# contra4688.net
KiCad netlist of a schematic drawn in EAGLE
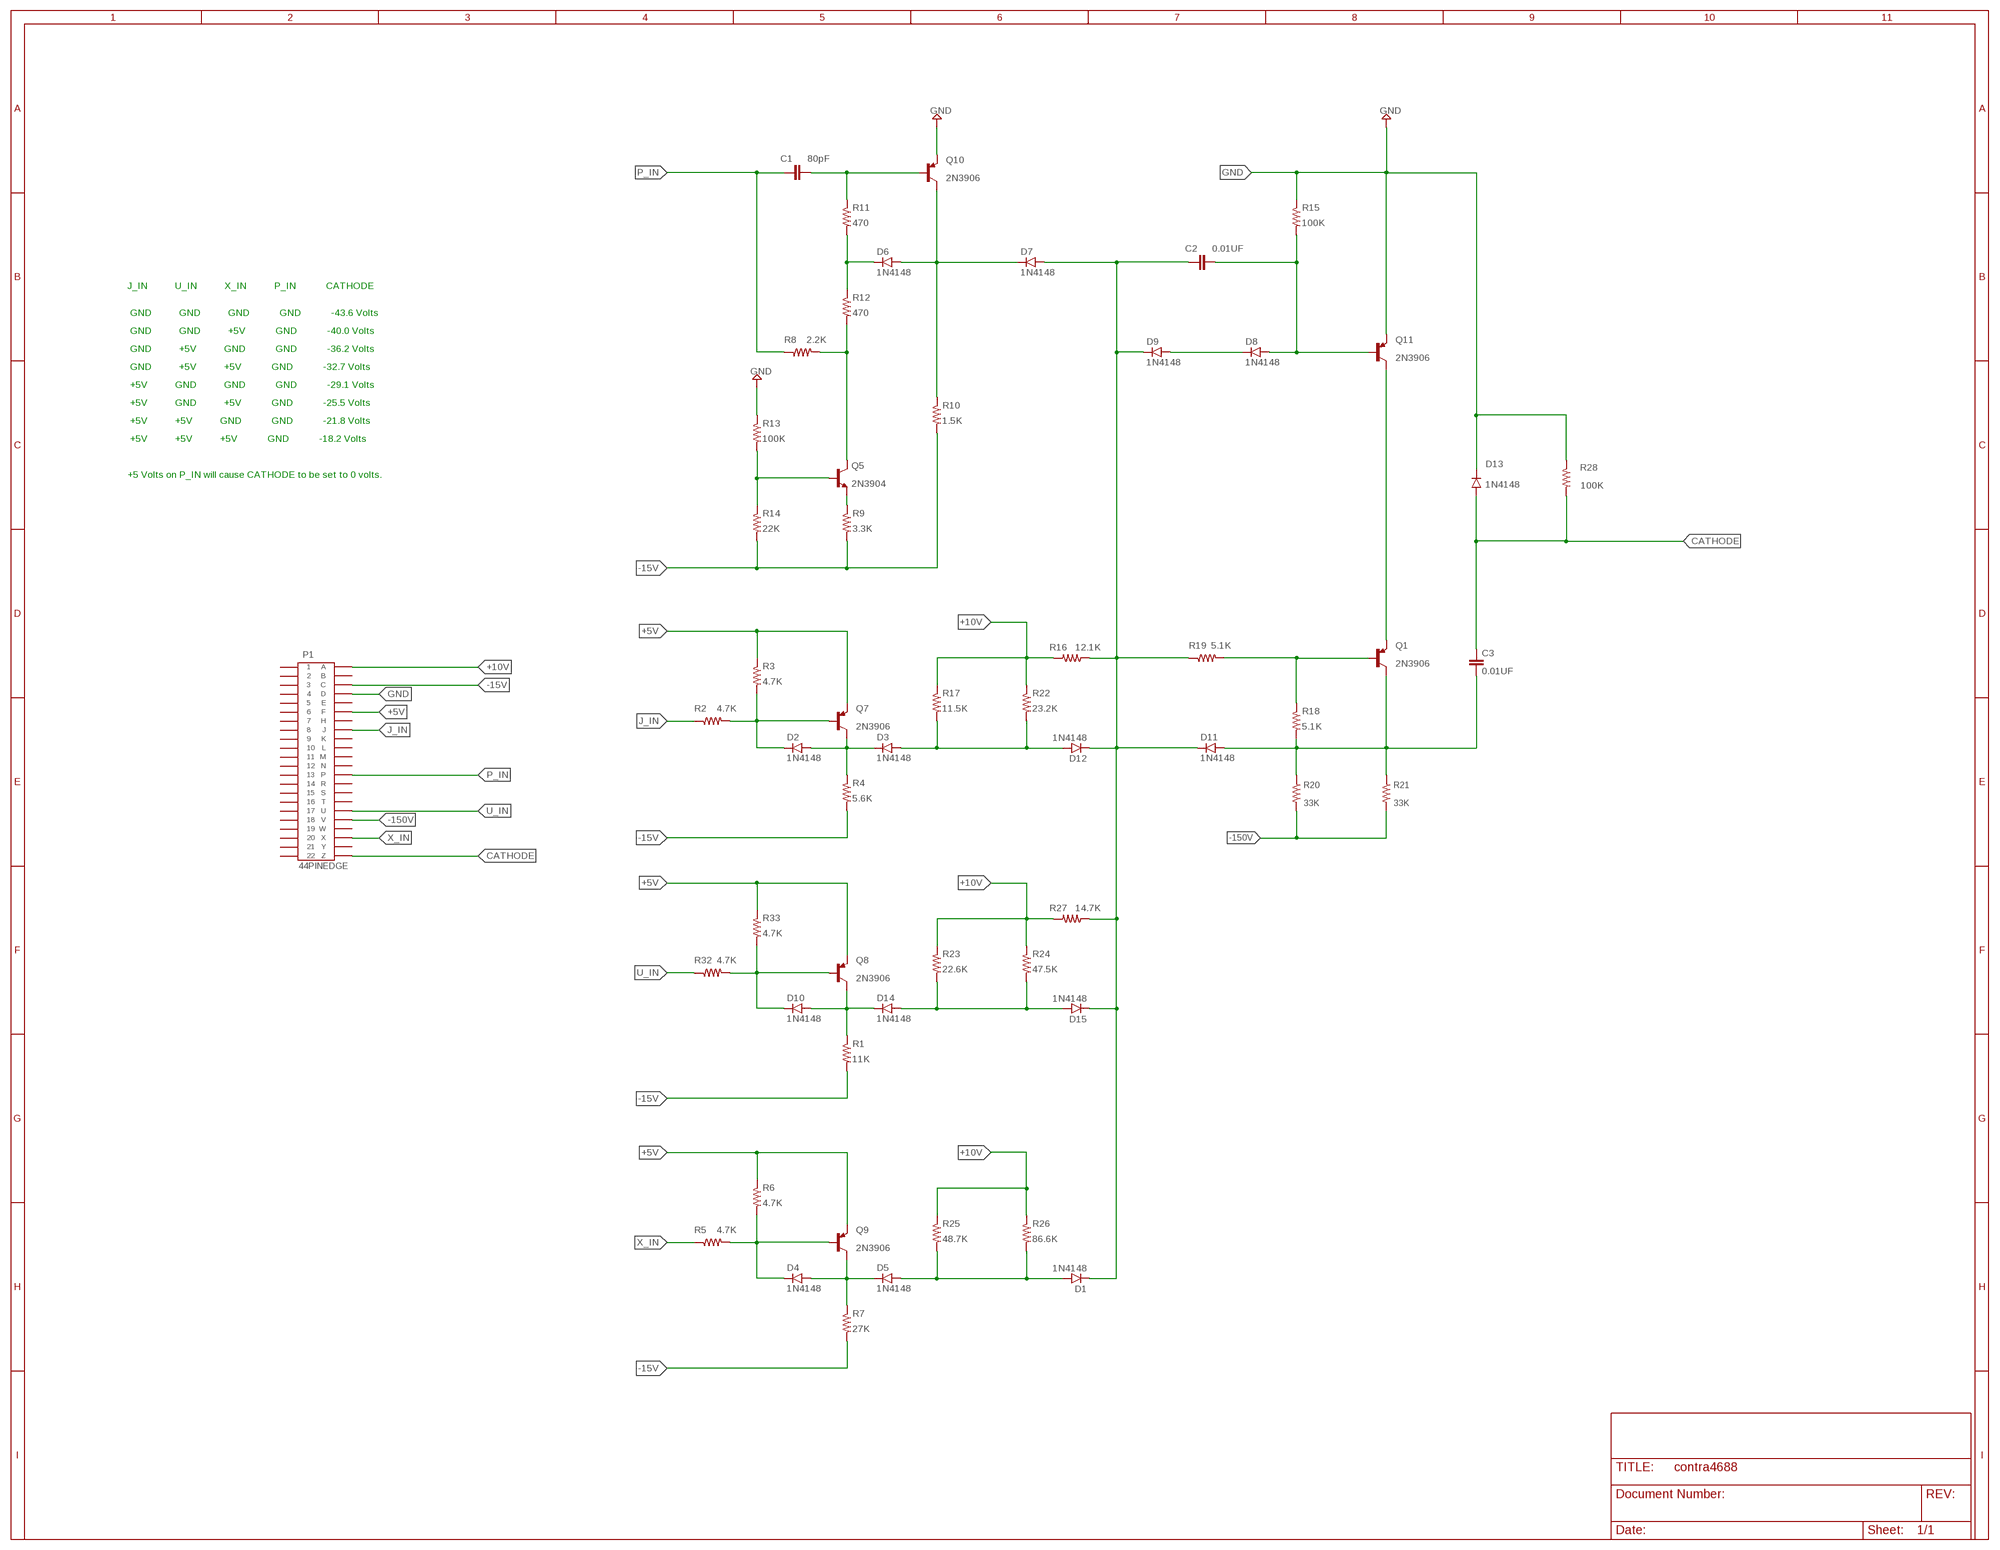
[diagram p0: schematic, sheet 1]

(export (version "E")
  (design (tool "Eeschema 10.0.6"))
  (components
    (comp (ref "C1")
      (value "80pF")
      (footprint "eagle-import:5MM_TH")
      (libsource (lib "eagle-import") (part "CAP_5MM"))
    )
    (comp (ref "C2")
      (value "0.01UF")
      (footprint "eagle-import:5MM_TH")
      (libsource (lib "eagle-import") (part "CAP_5MM"))
    )
    (comp (ref "C3")
      (value "0.01UF")
      (footprint "eagle-import:5MM_TH")
      (libsource (lib "eagle-import") (part "CAP_5MM"))
    )
    (comp (ref "D1")
      (value "1N4148")
      (footprint "eagle-import:DO35-7")
      (libsource (lib "eagle-import") (part "1N4148"))
    )
    (comp (ref "D2")
      (value "1N4148")
      (footprint "eagle-import:DO35-7")
      (libsource (lib "eagle-import") (part "1N4148"))
    )
    (comp (ref "D3")
      (value "1N4148")
      (footprint "eagle-import:DO35-7")
      (libsource (lib "eagle-import") (part "1N4148"))
    )
    (comp (ref "D4")
      (value "1N4148")
      (footprint "eagle-import:DO35-7")
      (libsource (lib "eagle-import") (part "1N4148"))
    )
    (comp (ref "D5")
      (value "1N4148")
      (footprint "eagle-import:DO35-7")
      (libsource (lib "eagle-import") (part "1N4148"))
    )
    (comp (ref "D6")
      (value "1N4148")
      (footprint "eagle-import:DO35-7")
      (libsource (lib "eagle-import") (part "1N4148"))
    )
    (comp (ref "D7")
      (value "1N4148")
      (footprint "eagle-import:DO35-7")
      (libsource (lib "eagle-import") (part "1N4148"))
    )
    (comp (ref "D8")
      (value "1N4148")
      (footprint "eagle-import:DO35-7")
      (libsource (lib "eagle-import") (part "1N4148"))
    )
    (comp (ref "D9")
      (value "1N4148")
      (footprint "eagle-import:DO35-7")
      (libsource (lib "eagle-import") (part "1N4148"))
    )
    (comp (ref "D10")
      (value "1N4148")
      (footprint "eagle-import:DO35-7")
      (libsource (lib "eagle-import") (part "1N4148"))
    )
    (comp (ref "D11")
      (value "1N4148")
      (footprint "eagle-import:DO35-7")
      (libsource (lib "eagle-import") (part "1N4148"))
    )
    (comp (ref "D12")
      (value "1N4148")
      (footprint "eagle-import:DO35-7")
      (libsource (lib "eagle-import") (part "1N4148"))
    )
    (comp (ref "D13")
      (value "1N4148")
      (footprint "eagle-import:DO35-7")
      (libsource (lib "eagle-import") (part "1N4148"))
    )
    (comp (ref "D14")
      (value "1N4148")
      (footprint "eagle-import:DO35-7")
      (libsource (lib "eagle-import") (part "1N4148"))
    )
    (comp (ref "D15")
      (value "1N4148")
      (footprint "eagle-import:DO35-7")
      (libsource (lib "eagle-import") (part "1N4148"))
    )
    (comp (ref "P1")
      (value "44PINEDGE")
      (footprint "eagle-import:44PINEDGE")
      (libsource (lib "eagle-import") (part "44PINEDGE"))
    )
    (comp (ref "Q1")
      (value "2N3906")
      (footprint "eagle-import:TO92")
      (libsource (lib "eagle-import") (part "2N3906"))
    )
    (comp (ref "Q5")
      (value "2N3904")
      (footprint "eagle-import:TO92")
      (libsource (lib "eagle-import") (part "2N3904"))
    )
    (comp (ref "Q7")
      (value "2N3906")
      (footprint "eagle-import:TO92")
      (libsource (lib "eagle-import") (part "2N3906"))
    )
    (comp (ref "Q8")
      (value "2N3906")
      (footprint "eagle-import:TO92")
      (libsource (lib "eagle-import") (part "2N3906"))
    )
    (comp (ref "Q9")
      (value "2N3906")
      (footprint "eagle-import:TO92")
      (libsource (lib "eagle-import") (part "2N3906"))
    )
    (comp (ref "Q10")
      (value "2N3906")
      (footprint "eagle-import:TO92")
      (libsource (lib "eagle-import") (part "2N3906"))
    )
    (comp (ref "Q11")
      (value "2N3906")
      (footprint "eagle-import:TO92")
      (libsource (lib "eagle-import") (part "2N3906"))
    )
    (comp (ref "R1")
      (value "11K")
      (footprint "eagle-import:0207_10")
      (libsource (lib "eagle-import") (part "R-1/4WATT"))
    )
    (comp (ref "R2")
      (value "4.7K")
      (footprint "eagle-import:0207_10")
      (libsource (lib "eagle-import") (part "R-1/4WATT"))
    )
    (comp (ref "R3")
      (value "4.7K")
      (footprint "eagle-import:0207_10")
      (libsource (lib "eagle-import") (part "R-1/4WATT"))
    )
    (comp (ref "R4")
      (value "5.6K")
      (footprint "eagle-import:0207_10")
      (libsource (lib "eagle-import") (part "R-1/4WATT"))
    )
    (comp (ref "R5")
      (value "4.7K")
      (footprint "eagle-import:0207_10")
      (libsource (lib "eagle-import") (part "R-1/4WATT"))
    )
    (comp (ref "R6")
      (value "4.7K")
      (footprint "eagle-import:0207_10")
      (libsource (lib "eagle-import") (part "R-1/4WATT"))
    )
    (comp (ref "R7")
      (value "27K")
      (footprint "eagle-import:0207_10")
      (libsource (lib "eagle-import") (part "R-1/4WATT"))
    )
    (comp (ref "R8")
      (value "2.2K")
      (footprint "eagle-import:0207_10")
      (libsource (lib "eagle-import") (part "R-1/4WATT"))
    )
    (comp (ref "R9")
      (value "3.3K")
      (footprint "eagle-import:0207_10")
      (libsource (lib "eagle-import") (part "R-1/4WATT"))
    )
    (comp (ref "R10")
      (value "1.5K")
      (footprint "eagle-import:0207_10")
      (libsource (lib "eagle-import") (part "R-1/4WATT"))
    )
    (comp (ref "R11")
      (value "470")
      (footprint "eagle-import:0207_10")
      (libsource (lib "eagle-import") (part "R-1/4WATT"))
    )
    (comp (ref "R12")
      (value "470")
      (footprint "eagle-import:0207_10")
      (libsource (lib "eagle-import") (part "R-1/4WATT"))
    )
    (comp (ref "R13")
      (value "100K")
      (footprint "eagle-import:0207_10")
      (libsource (lib "eagle-import") (part "R-1/4WATT"))
    )
    (comp (ref "R14")
      (value "22K")
      (footprint "eagle-import:0207_10")
      (libsource (lib "eagle-import") (part "R-1/4WATT"))
    )
    (comp (ref "R15")
      (value "100K")
      (footprint "eagle-import:0207_10")
      (libsource (lib "eagle-import") (part "R-1/4WATT"))
    )
    (comp (ref "R16")
      (value "12.1K")
      (footprint "eagle-import:0207_10")
      (libsource (lib "eagle-import") (part "R-1/4WATT"))
    )
    (comp (ref "R17")
      (value "11.5K")
      (footprint "eagle-import:0207_10")
      (libsource (lib "eagle-import") (part "R-1/4WATT"))
    )
    (comp (ref "R18")
      (value "5.1K")
      (footprint "eagle-import:0207_10")
      (libsource (lib "eagle-import") (part "R-1/4WATT"))
    )
    (comp (ref "R19")
      (value "5.1K")
      (footprint "eagle-import:0207_10")
      (libsource (lib "eagle-import") (part "R-1/4WATT"))
    )
    (comp (ref "R20")
      (value "33K")
      (footprint "eagle-import:RR02")
      (libsource (lib "eagle-import") (part "RES33K2W"))
    )
    (comp (ref "R21")
      (value "33K")
      (footprint "eagle-import:RR02")
      (libsource (lib "eagle-import") (part "RES33K2W"))
    )
    (comp (ref "R22")
      (value "23.2K")
      (footprint "eagle-import:0207_10")
      (libsource (lib "eagle-import") (part "R-1/4WATT"))
    )
    (comp (ref "R23")
      (value "22.6K")
      (footprint "eagle-import:0207_10")
      (libsource (lib "eagle-import") (part "R-1/4WATT"))
    )
    (comp (ref "R24")
      (value "47.5K")
      (footprint "eagle-import:0207_10")
      (libsource (lib "eagle-import") (part "R-1/4WATT"))
    )
    (comp (ref "R25")
      (value "48.7K")
      (footprint "eagle-import:0207_10")
      (libsource (lib "eagle-import") (part "R-1/4WATT"))
    )
    (comp (ref "R26")
      (value "86.6K")
      (footprint "eagle-import:0207_10")
      (libsource (lib "eagle-import") (part "R-1/4WATT"))
    )
    (comp (ref "R27")
      (value "14.7K")
      (footprint "eagle-import:0207_10")
      (libsource (lib "eagle-import") (part "R-1/4WATT"))
    )
    (comp (ref "R28")
      (value "100K")
      (footprint "eagle-import:0207_10")
      (libsource (lib "eagle-import") (part "R-1/4WATT"))
    )
    (comp (ref "R32")
      (value "4.7K")
      (footprint "eagle-import:0207_10")
      (libsource (lib "eagle-import") (part "R-1/4WATT"))
    )
    (comp (ref "R33")
      (value "4.7K")
      (footprint "eagle-import:0207_10")
      (libsource (lib "eagle-import") (part "R-1/4WATT"))
    )
  )
  (nets
    (net (code "1") (name "+5V") (class "Default")
      (node (ref "P1") (pin "F") (pinfunction "F_F") (pintype "passive"))
      (node (ref "Q7") (pin "3") (pinfunction "E_3") (pintype "passive"))
      (node (ref "Q8") (pin "3") (pinfunction "E_3") (pintype "passive"))
      (node (ref "Q9") (pin "3") (pinfunction "E_3") (pintype "passive"))
      (node (ref "R3") (pin "1") (pinfunction "P$1_1") (pintype "passive"))
      (node (ref "R33") (pin "1") (pinfunction "P$1_1") (pintype "passive"))
      (node (ref "R6") (pin "1") (pinfunction "P$1_1") (pintype "passive"))
    )
    (net (code "2") (name "+10V") (class "Default")
      (node (ref "P1") (pin "A") (pinfunction "A_A") (pintype "passive"))
      (node (ref "R16") (pin "2") (pinfunction "P$2_2") (pintype "passive"))
      (node (ref "R17") (pin "1") (pinfunction "P$1_1") (pintype "passive"))
      (node (ref "R22") (pin "1") (pinfunction "P$1_1") (pintype "passive"))
      (node (ref "R23") (pin "1") (pinfunction "P$1_1") (pintype "passive"))
      (node (ref "R24") (pin "1") (pinfunction "P$1_1") (pintype "passive"))
      (node (ref "R25") (pin "1") (pinfunction "P$1_1") (pintype "passive"))
      (node (ref "R26") (pin "1") (pinfunction "P$1_1") (pintype "passive"))
      (node (ref "R27") (pin "2") (pinfunction "P$2_2") (pintype "passive"))
    )
    (net (code "3") (name "-15V") (class "Default")
      (node (ref "P1") (pin "C") (pinfunction "C_C") (pintype "passive"))
      (node (ref "R1") (pin "2") (pinfunction "P$2_2") (pintype "passive"))
      (node (ref "R10") (pin "2") (pinfunction "P$2_2") (pintype "passive"))
      (node (ref "R14") (pin "2") (pinfunction "P$2_2") (pintype "passive"))
      (node (ref "R4") (pin "2") (pinfunction "P$2_2") (pintype "passive"))
      (node (ref "R7") (pin "2") (pinfunction "P$2_2") (pintype "passive"))
      (node (ref "R9") (pin "2") (pinfunction "P$2_2") (pintype "passive"))
    )
    (net (code "4") (name "-150V") (class "Default")
      (node (ref "P1") (pin "V") (pinfunction "V_V") (pintype "passive"))
      (node (ref "R20") (pin "2") (pinfunction "P$2_2") (pintype "passive"))
      (node (ref "R21") (pin "2") (pinfunction "P$2_2") (pintype "passive"))
    )
    (net (code "5") (name "CATHODE") (class "Default")
      (node (ref "C3") (pin "1") (pinfunction "1_1") (pintype "passive"))
      (node (ref "D13") (pin "A") (pinfunction "A_A") (pintype "passive"))
      (node (ref "P1") (pin "Z") (pinfunction "Z_Z") (pintype "passive"))
      (node (ref "R28") (pin "2") (pinfunction "P$2_2") (pintype "passive"))
    )
    (net (code "6") (name "GND") (class "Default")
      (node (ref "D13") (pin "C") (pinfunction "C_C") (pintype "passive"))
      (node (ref "P1") (pin "D") (pinfunction "D_D") (pintype "passive"))
      (node (ref "Q10") (pin "3") (pinfunction "E_3") (pintype "passive"))
      (node (ref "Q11") (pin "3") (pinfunction "E_3") (pintype "passive"))
      (node (ref "R13") (pin "1") (pinfunction "P$1_1") (pintype "passive"))
      (node (ref "R15") (pin "1") (pinfunction "P$1_1") (pintype "passive"))
      (node (ref "R28") (pin "1") (pinfunction "P$1_1") (pintype "passive"))
    )
    (net (code "7") (name "J_IN") (class "Default")
      (node (ref "P1") (pin "J") (pinfunction "J_J") (pintype "passive"))
      (node (ref "R2") (pin "1") (pinfunction "P$1_1") (pintype "passive"))
    )
    (net (code "8") (name "Net-(D8-PadC)") (class "Default")
      (node (ref "D8") (pin "C") (pinfunction "C_C") (pintype "passive"))
      (node (ref "D9") (pin "A") (pinfunction "A_A") (pintype "passive"))
    )
    (net (code "9") (name "Net-(Q1-B)") (class "Default")
      (node (ref "Q1") (pin "2") (pinfunction "B_2") (pintype "passive"))
      (node (ref "R18") (pin "1") (pinfunction "P$1_1") (pintype "passive"))
      (node (ref "R19") (pin "2") (pinfunction "P$2_2") (pintype "passive"))
    )
    (net (code "10") (name "Net-(Q1-C)") (class "Default")
      (node (ref "C3") (pin "2") (pinfunction "2_2") (pintype "passive"))
      (node (ref "D11") (pin "A") (pinfunction "A_A") (pintype "passive"))
      (node (ref "Q1") (pin "1") (pinfunction "C_1") (pintype "passive"))
      (node (ref "R18") (pin "2") (pinfunction "P$2_2") (pintype "passive"))
      (node (ref "R20") (pin "1") (pinfunction "P$1_1") (pintype "passive"))
      (node (ref "R21") (pin "1") (pinfunction "P$1_1") (pintype "passive"))
    )
    (net (code "11") (name "Net-(Q1-E)") (class "Default")
      (node (ref "Q1") (pin "3") (pinfunction "E_3") (pintype "passive"))
      (node (ref "Q11") (pin "1") (pinfunction "C_1") (pintype "passive"))
    )
    (net (code "12") (name "Net-(Q5-B)") (class "Default")
      (node (ref "Q5") (pin "2") (pinfunction "B_2") (pintype "passive"))
      (node (ref "R13") (pin "2") (pinfunction "P$2_2") (pintype "passive"))
      (node (ref "R14") (pin "1") (pinfunction "P$1_1") (pintype "passive"))
    )
    (net (code "13") (name "Net-(Q5-C)") (class "Default")
      (node (ref "Q5") (pin "1") (pinfunction "C_1") (pintype "passive"))
      (node (ref "R12") (pin "2") (pinfunction "P$2_2") (pintype "passive"))
      (node (ref "R8") (pin "2") (pinfunction "P$2_2") (pintype "passive"))
    )
    (net (code "14") (name "Net-(Q5-E)") (class "Default")
      (node (ref "Q5") (pin "3") (pinfunction "E_3") (pintype "passive"))
      (node (ref "R9") (pin "1") (pinfunction "P$1_1") (pintype "passive"))
    )
    (net (code "15") (name "Net-(Q7-B)") (class "Default")
      (node (ref "D2") (pin "C") (pinfunction "C_C") (pintype "passive"))
      (node (ref "Q7") (pin "2") (pinfunction "B_2") (pintype "passive"))
      (node (ref "R2") (pin "2") (pinfunction "P$2_2") (pintype "passive"))
      (node (ref "R3") (pin "2") (pinfunction "P$2_2") (pintype "passive"))
    )
    (net (code "16") (name "Net-(Q7-C)") (class "Default")
      (node (ref "D2") (pin "A") (pinfunction "A_A") (pintype "passive"))
      (node (ref "D3") (pin "C") (pinfunction "C_C") (pintype "passive"))
      (node (ref "Q7") (pin "1") (pinfunction "C_1") (pintype "passive"))
      (node (ref "R4") (pin "1") (pinfunction "P$1_1") (pintype "passive"))
    )
    (net (code "17") (name "Net-(Q8-B)") (class "Default")
      (node (ref "D10") (pin "C") (pinfunction "C_C") (pintype "passive"))
      (node (ref "Q8") (pin "2") (pinfunction "B_2") (pintype "passive"))
      (node (ref "R32") (pin "2") (pinfunction "P$2_2") (pintype "passive"))
      (node (ref "R33") (pin "2") (pinfunction "P$2_2") (pintype "passive"))
    )
    (net (code "18") (name "Net-(Q8-C)") (class "Default")
      (node (ref "D10") (pin "A") (pinfunction "A_A") (pintype "passive"))
      (node (ref "D14") (pin "C") (pinfunction "C_C") (pintype "passive"))
      (node (ref "Q8") (pin "1") (pinfunction "C_1") (pintype "passive"))
      (node (ref "R1") (pin "1") (pinfunction "P$1_1") (pintype "passive"))
    )
    (net (code "19") (name "Net-(Q9-B)") (class "Default")
      (node (ref "D4") (pin "C") (pinfunction "C_C") (pintype "passive"))
      (node (ref "Q9") (pin "2") (pinfunction "B_2") (pintype "passive"))
      (node (ref "R5") (pin "2") (pinfunction "P$2_2") (pintype "passive"))
      (node (ref "R6") (pin "2") (pinfunction "P$2_2") (pintype "passive"))
    )
    (net (code "20") (name "Net-(Q9-C)") (class "Default")
      (node (ref "D4") (pin "A") (pinfunction "A_A") (pintype "passive"))
      (node (ref "D5") (pin "C") (pinfunction "C_C") (pintype "passive"))
      (node (ref "Q9") (pin "1") (pinfunction "C_1") (pintype "passive"))
      (node (ref "R7") (pin "1") (pinfunction "P$1_1") (pintype "passive"))
    )
    (net (code "21") (name "Net-(Q10-B)") (class "Default")
      (node (ref "C1") (pin "2") (pinfunction "2_2") (pintype "passive"))
      (node (ref "Q10") (pin "2") (pinfunction "B_2") (pintype "passive"))
      (node (ref "R11") (pin "1") (pinfunction "P$1_1") (pintype "passive"))
    )
    (net (code "22") (name "Net-(Q10-C)") (class "Default")
      (node (ref "D6") (pin "A") (pinfunction "A_A") (pintype "passive"))
      (node (ref "D7") (pin "C") (pinfunction "C_C") (pintype "passive"))
      (node (ref "Q10") (pin "1") (pinfunction "C_1") (pintype "passive"))
      (node (ref "R10") (pin "1") (pinfunction "P$1_1") (pintype "passive"))
    )
    (net (code "23") (name "Net-(Q11-B)") (class "Default")
      (node (ref "C2") (pin "2") (pinfunction "2_2") (pintype "passive"))
      (node (ref "D8") (pin "A") (pinfunction "A_A") (pintype "passive"))
      (node (ref "Q11") (pin "2") (pinfunction "B_2") (pintype "passive"))
      (node (ref "R15") (pin "2") (pinfunction "P$2_2") (pintype "passive"))
    )
    (net (code "24") (name "Net-(R11-P$2)") (class "Default")
      (node (ref "D6") (pin "C") (pinfunction "C_C") (pintype "passive"))
      (node (ref "R11") (pin "2") (pinfunction "P$2_2") (pintype "passive"))
      (node (ref "R12") (pin "1") (pinfunction "P$1_1") (pintype "passive"))
    )
    (net (code "25") (name "Net-(R16-P$1)") (class "Default")
      (node (ref "C2") (pin "1") (pinfunction "1_1") (pintype "passive"))
      (node (ref "D1") (pin "C") (pinfunction "C_C") (pintype "passive"))
      (node (ref "D11") (pin "C") (pinfunction "C_C") (pintype "passive"))
      (node (ref "D12") (pin "C") (pinfunction "C_C") (pintype "passive"))
      (node (ref "D15") (pin "C") (pinfunction "C_C") (pintype "passive"))
      (node (ref "D7") (pin "A") (pinfunction "A_A") (pintype "passive"))
      (node (ref "D9") (pin "C") (pinfunction "C_C") (pintype "passive"))
      (node (ref "R16") (pin "1") (pinfunction "P$1_1") (pintype "passive"))
      (node (ref "R19") (pin "1") (pinfunction "P$1_1") (pintype "passive"))
      (node (ref "R27") (pin "1") (pinfunction "P$1_1") (pintype "passive"))
    )
    (net (code "26") (name "Net-(R17-P$2)") (class "Default")
      (node (ref "D12") (pin "A") (pinfunction "A_A") (pintype "passive"))
      (node (ref "D3") (pin "A") (pinfunction "A_A") (pintype "passive"))
      (node (ref "R17") (pin "2") (pinfunction "P$2_2") (pintype "passive"))
      (node (ref "R22") (pin "2") (pinfunction "P$2_2") (pintype "passive"))
    )
    (net (code "27") (name "Net-(R23-P$2)") (class "Default")
      (node (ref "D14") (pin "A") (pinfunction "A_A") (pintype "passive"))
      (node (ref "D15") (pin "A") (pinfunction "A_A") (pintype "passive"))
      (node (ref "R23") (pin "2") (pinfunction "P$2_2") (pintype "passive"))
      (node (ref "R24") (pin "2") (pinfunction "P$2_2") (pintype "passive"))
    )
    (net (code "28") (name "Net-(R25-P$2)") (class "Default")
      (node (ref "D1") (pin "A") (pinfunction "A_A") (pintype "passive"))
      (node (ref "D5") (pin "A") (pinfunction "A_A") (pintype "passive"))
      (node (ref "R25") (pin "2") (pinfunction "P$2_2") (pintype "passive"))
      (node (ref "R26") (pin "2") (pinfunction "P$2_2") (pintype "passive"))
    )
    (net (code "29") (name "P_IN") (class "Default")
      (node (ref "C1") (pin "1") (pinfunction "1_1") (pintype "passive"))
      (node (ref "P1") (pin "P") (pinfunction "P_P") (pintype "passive"))
      (node (ref "R8") (pin "1") (pinfunction "P$1_1") (pintype "passive"))
    )
    (net (code "30") (name "U_IN") (class "Default")
      (node (ref "P1") (pin "U") (pinfunction "U_U") (pintype "passive"))
      (node (ref "R32") (pin "1") (pinfunction "P$1_1") (pintype "passive"))
    )
    (net (code "31") (name "X_IN") (class "Default")
      (node (ref "P1") (pin "X") (pinfunction "X_X") (pintype "passive"))
      (node (ref "R5") (pin "1") (pinfunction "P$1_1") (pintype "passive"))
    )
    (net (code "32") (name "unconnected-(P1-Pad1)") (class "Default")
      (node (ref "P1") (pin "1") (pinfunction "1_1") (pintype "passive"))
    )
    (net (code "33") (name "unconnected-(P1-Pad2)") (class "Default")
      (node (ref "P1") (pin "2") (pinfunction "2_2") (pintype "passive"))
    )
    (net (code "34") (name "unconnected-(P1-Pad3)") (class "Default")
      (node (ref "P1") (pin "3") (pinfunction "3_3") (pintype "passive"))
    )
    (net (code "35") (name "unconnected-(P1-Pad4)") (class "Default")
      (node (ref "P1") (pin "4") (pinfunction "4_4") (pintype "passive"))
    )
    (net (code "36") (name "unconnected-(P1-Pad5)") (class "Default")
      (node (ref "P1") (pin "5") (pinfunction "5_5") (pintype "passive"))
    )
    (net (code "37") (name "unconnected-(P1-Pad6)") (class "Default")
      (node (ref "P1") (pin "6") (pinfunction "6_6") (pintype "passive"))
    )
    (net (code "38") (name "unconnected-(P1-Pad7)") (class "Default")
      (node (ref "P1") (pin "7") (pinfunction "7_7") (pintype "passive"))
    )
    (net (code "39") (name "unconnected-(P1-Pad8)") (class "Default")
      (node (ref "P1") (pin "8") (pinfunction "8_8") (pintype "passive"))
    )
    (net (code "40") (name "unconnected-(P1-Pad9)") (class "Default")
      (node (ref "P1") (pin "9") (pinfunction "9_9") (pintype "passive"))
    )
    (net (code "41") (name "unconnected-(P1-Pad10)") (class "Default")
      (node (ref "P1") (pin "10") (pinfunction "10_10") (pintype "passive"))
    )
    (net (code "42") (name "unconnected-(P1-Pad11)") (class "Default")
      (node (ref "P1") (pin "11") (pinfunction "11_11") (pintype "passive"))
    )
    (net (code "43") (name "unconnected-(P1-Pad12)") (class "Default")
      (node (ref "P1") (pin "12") (pinfunction "12_12") (pintype "passive"))
    )
    (net (code "44") (name "unconnected-(P1-Pad13)") (class "Default")
      (node (ref "P1") (pin "13") (pinfunction "13_13") (pintype "passive"))
    )
    (net (code "45") (name "unconnected-(P1-Pad14)") (class "Default")
      (node (ref "P1") (pin "14") (pinfunction "14_14") (pintype "passive"))
    )
    (net (code "46") (name "unconnected-(P1-Pad15)") (class "Default")
      (node (ref "P1") (pin "15") (pinfunction "15_15") (pintype "passive"))
    )
    (net (code "47") (name "unconnected-(P1-Pad16)") (class "Default")
      (node (ref "P1") (pin "16") (pinfunction "16_16") (pintype "passive"))
    )
    (net (code "48") (name "unconnected-(P1-Pad17)") (class "Default")
      (node (ref "P1") (pin "17") (pinfunction "17_17") (pintype "passive"))
    )
    (net (code "49") (name "unconnected-(P1-Pad18)") (class "Default")
      (node (ref "P1") (pin "18") (pinfunction "18_18") (pintype "passive"))
    )
    (net (code "50") (name "unconnected-(P1-Pad19)") (class "Default")
      (node (ref "P1") (pin "19") (pinfunction "19_19") (pintype "passive"))
    )
    (net (code "51") (name "unconnected-(P1-Pad20)") (class "Default")
      (node (ref "P1") (pin "20") (pinfunction "20_20") (pintype "passive"))
    )
    (net (code "52") (name "unconnected-(P1-Pad21)") (class "Default")
      (node (ref "P1") (pin "21") (pinfunction "21_21") (pintype "passive"))
    )
    (net (code "53") (name "unconnected-(P1-Pad22)") (class "Default")
      (node (ref "P1") (pin "22") (pinfunction "22_22") (pintype "passive"))
    )
    (net (code "54") (name "unconnected-(P1-PadB)") (class "Default")
      (node (ref "P1") (pin "B") (pinfunction "B_B") (pintype "passive"))
    )
    (net (code "55") (name "unconnected-(P1-PadE)") (class "Default")
      (node (ref "P1") (pin "E") (pinfunction "E_E") (pintype "passive"))
    )
    (net (code "56") (name "unconnected-(P1-PadH)") (class "Default")
      (node (ref "P1") (pin "H") (pinfunction "H_H") (pintype "passive"))
    )
    (net (code "57") (name "unconnected-(P1-PadK)") (class "Default")
      (node (ref "P1") (pin "K") (pinfunction "K_K") (pintype "passive"))
    )
    (net (code "58") (name "unconnected-(P1-PadL)") (class "Default")
      (node (ref "P1") (pin "L") (pinfunction "L_L") (pintype "passive"))
    )
    (net (code "59") (name "unconnected-(P1-PadM)") (class "Default")
      (node (ref "P1") (pin "M") (pinfunction "M_M") (pintype "passive"))
    )
    (net (code "60") (name "unconnected-(P1-PadN)") (class "Default")
      (node (ref "P1") (pin "N") (pinfunction "N_N") (pintype "passive"))
    )
    (net (code "61") (name "unconnected-(P1-PadR)") (class "Default")
      (node (ref "P1") (pin "R") (pinfunction "R_R") (pintype "passive"))
    )
    (net (code "62") (name "unconnected-(P1-PadS)") (class "Default")
      (node (ref "P1") (pin "S") (pinfunction "S_S") (pintype "passive"))
    )
    (net (code "63") (name "unconnected-(P1-PadT)") (class "Default")
      (node (ref "P1") (pin "T") (pinfunction "T_T") (pintype "passive"))
    )
    (net (code "64") (name "unconnected-(P1-PadW)") (class "Default")
      (node (ref "P1") (pin "W") (pinfunction "W_W") (pintype "passive"))
    )
    (net (code "65") (name "unconnected-(P1-PadY)") (class "Default")
      (node (ref "P1") (pin "Y") (pinfunction "Y_Y") (pintype "passive"))
    )
  )
)
